# FM-Radio-Simple-Receiver-Dip1.net
KiCad netlist of a schematic drawn in EAGLE
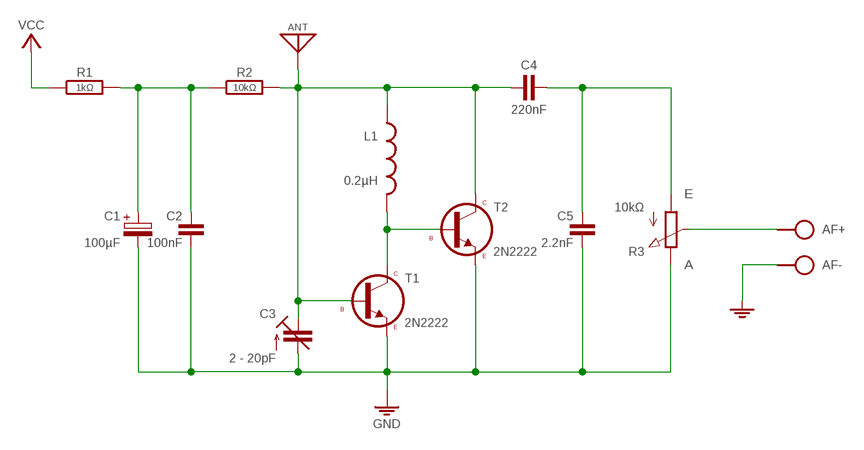
[diagram p0: schematic, sheet 1]

(export (version "E")
  (design (tool "Eeschema 10.0.6"))
  (components
    (comp (ref "AF")
      (value "SPAD+--+")
      (footprint "eagle-import:SPAD-+")
      (libsource (lib "eagle-import") (part "SPAD+--+"))
    )
    (comp (ref "ANT")
      (value "ANT")
      (footprint "eagle-import:SPAD")
      (libsource (lib "eagle-import") (part "ANT"))
    )
    (comp (ref "BAT")
      (value "VCC_GNDL")
      (footprint "eagle-import:SPAD-+")
      (libsource (lib "eagle-import") (part "VCC_GNDL"))
    )
    (comp (ref "C1")
      (value "100µF")
      (footprint "eagle-import:E2,5-5_V")
      (libsource (lib "eagle-import") (part "CPOLE2,5-5/V"))
    )
    (comp (ref "C2")
      (value "100nF")
      (footprint "eagle-import:C050-020X036_V")
      (libsource (lib "eagle-import") (part "C050-020X036/V"))
    )
    (comp (ref "C3")
      (value "2 - 20pF")
      (footprint "eagle-import:TRIM-2222-808")
      (libsource (lib "eagle-import") (part "C-TR-PH201272222-808-2PIND"))
    )
    (comp (ref "C4")
      (value "220nF")
      (footprint "eagle-import:C050-020X044")
      (libsource (lib "eagle-import") (part "C-H050-020X044"))
    )
    (comp (ref "C5")
      (value "2.2nF")
      (footprint "eagle-import:C050-020X036_V")
      (libsource (lib "eagle-import") (part "C050-020X036/V"))
    )
    (comp (ref "L1")
      (value "0.2µH")
      (footprint "eagle-import:L-10_10Y")
      (libsource (lib "eagle-import") (part "L10/10Y"))
    )
    (comp (ref "R1")
      (value "1kΩ")
      (footprint "eagle-import:0204_10")
      (libsource (lib "eagle-import") (part "R-H0204/10"))
    )
    (comp (ref "R2")
      (value "10kΩ")
      (footprint "eagle-import:0204_10")
      (libsource (lib "eagle-import") (part "R-H0204/10"))
    )
    (comp (ref "R3")
      (value "10kΩ")
      (footprint "eagle-import:CONN-3P")
      (libsource (lib "eagle-import") (part "POT-3P"))
    )
    (comp (ref "T1")
      (value "2N2222")
      (footprint "eagle-import:TO92")
      (libsource (lib "eagle-import") (part "2N2222"))
    )
    (comp (ref "T2")
      (value "2N2222")
      (footprint "eagle-import:TO92")
      (libsource (lib "eagle-import") (part "2N2222"))
    )
  )
  (nets
    (net (code "1") (name "GND") (class "Default")
      (node (ref "AF") (pin "1") (pinfunction "P$1_1") (pintype "passive"))
      (node (ref "BAT") (pin "1") (pinfunction "GND_1") (pintype "power_in"))
      (node (ref "C1") (pin "-") (pinfunction "-_-") (pintype "passive"))
      (node (ref "C2") (pin "2") (pinfunction "2_2") (pintype "passive"))
      (node (ref "C3") (pin "2") (pinfunction "A_2") (pintype "passive"))
      (node (ref "C5") (pin "2") (pinfunction "2_2") (pintype "passive"))
      (node (ref "R3") (pin "3") (pinfunction "E_3") (pintype "passive"))
      (node (ref "T1") (pin "1") (pinfunction "E_1") (pintype "passive"))
      (node (ref "T2") (pin "1") (pinfunction "E_1") (pintype "passive"))
    )
    (net (code "2") (name "Net-(AFA-P$1)") (class "Default")
      (node (ref "AF") (pin "2") (pinfunction "P$1_2") (pintype "passive"))
      (node (ref "R3") (pin "2") (pinfunction "S_2") (pintype "passive"))
    )
    (net (code "3") (name "Net-(BATA-VCC)") (class "Default")
      (node (ref "BAT") (pin "2") (pinfunction "VCC_2") (pintype "power_in"))
      (node (ref "R1") (pin "1") (pinfunction "1_1") (pintype "passive"))
    )
    (net (code "4") (name "Net-(C1-Pad+)") (class "Default")
      (node (ref "C1") (pin "+") (pinfunction "+_+") (pintype "passive"))
      (node (ref "C2") (pin "1") (pinfunction "1_1") (pintype "passive"))
      (node (ref "R1") (pin "2") (pinfunction "2_2") (pintype "passive"))
      (node (ref "R2") (pin "1") (pinfunction "1_1") (pintype "passive"))
    )
    (net (code "5") (name "Net-(C3-E)") (class "Default")
      (node (ref "ANT") (pin "1") (pinfunction "1_1") (pintype "output"))
      (node (ref "C3") (pin "3") (pinfunction "E_3") (pintype "passive"))
      (node (ref "C4") (pin "1") (pinfunction "1_1") (pintype "passive"))
      (node (ref "L1") (pin "P$1") (pinfunction "1_P$1") (pintype "passive"))
      (node (ref "R2") (pin "2") (pinfunction "2_2") (pintype "passive"))
      (node (ref "T1") (pin "2") (pinfunction "B_2") (pintype "passive"))
      (node (ref "T2") (pin "3") (pinfunction "C_3") (pintype "passive"))
    )
    (net (code "6") (name "Net-(L1-2)") (class "Default")
      (node (ref "L1") (pin "P$2") (pinfunction "2_P$2") (pintype "passive"))
      (node (ref "T1") (pin "3") (pinfunction "C_3") (pintype "passive"))
      (node (ref "T2") (pin "2") (pinfunction "B_2") (pintype "passive"))
    )
    (net (code "7") (name "Net-(R3-A)") (class "Default")
      (node (ref "C4") (pin "2") (pinfunction "2_2") (pintype "passive"))
      (node (ref "C5") (pin "1") (pinfunction "1_1") (pintype "passive"))
      (node (ref "R3") (pin "1") (pinfunction "A_1") (pintype "passive"))
    )
  )
)
